# 01_MCU.net
KiCad netlist of a schematic drawn in Altium Designer
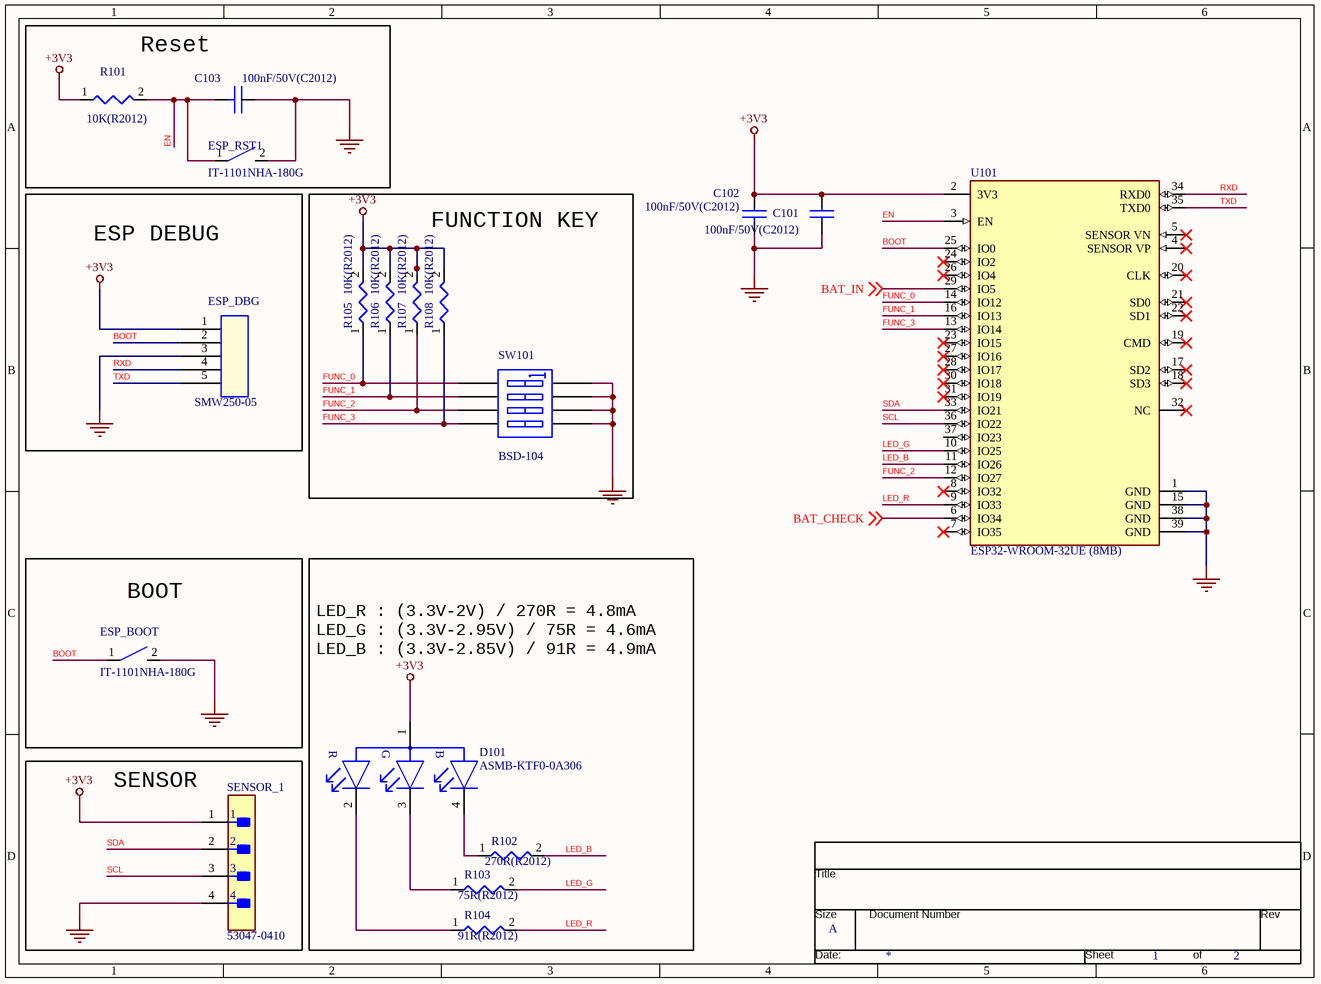
[diagram p0: 01_MCU.SchDoc]

(export (version "E")
  (design (tool "Eeschema 10.0.6"))
  (components
    (comp (ref "*")
      (value "TitleBlock0")
      (fields (field (name "PAGE COUNT") "2") (field (name "PAGE NUMBER") "1") (field (name "PAGE SIZE") "A"))
      (libsource (lib "*") (part "TitleBlock0"))
    )
    (comp (ref "C101") (value "100nF/50V(C2012)") (footprint "C2012") (libsource (lib "*") (part "CAP NP_0")))
    (comp (ref "C102") (value "100nF/50V(C2012)") (footprint "C2012") (libsource (lib "*") (part "CAP NP_0")))
    (comp (ref "C103") (value "100nF/50V(C2012)") (footprint "C2012") (libsource (lib "*") (part "C_0")))
    (comp (ref "D101")
      (value "ASMB-KTF0-0A306")
      (footprint "FP-PLCC-4-MFG")
      (description "LED RGB 4PLCC SMD")
      (fields
        (field (name "MANUFACTURER") "Broadcom")
        (field (name "OCTOPART") "https://octopart.com/asmb-ktf0-0a306-broadcom-87157377")
      )
      (libsource (lib "Altium Content Vault") (part "e0afb02c9a33798a4bdd6795f3df34c"))
    )
    (comp (ref "ESP_BOOT")
      (value "IT-1101NHA-180G")
      (footprint "SW_Tact_2p")
      (libsource (lib "*") (part "SWITCH"))
    )
    (comp (ref "ESP_DBG") (value "SMW250-05") (footprint "CON5267-05") (libsource (lib "*") (part "CON5")))
    (comp (ref "ESP_RST1")
      (value "IT-1101NHA-180G")
      (footprint "SW_Tact_2p")
      (libsource (lib "*") (part "SWITCH"))
    )
    (comp (ref "R101") (value "10K(R2012)") (footprint "R2012") (libsource (lib "*") (part "R_3")))
    (comp (ref "R102") (value "270R(R2012)") (footprint "R2012") (libsource (lib "*") (part "R_3")))
    (comp (ref "R103") (value "75R(R2012)") (footprint "R2012") (libsource (lib "*") (part "R_3")))
    (comp (ref "R104") (value "91R(R2012)") (footprint "R2012") (libsource (lib "*") (part "R_3")))
    (comp (ref "R105") (value "10K(R2012)") (footprint "R2012") (libsource (lib "*") (part "R_3")))
    (comp (ref "R106") (value "10K(R2012)") (footprint "R2012") (libsource (lib "*") (part "R_3")))
    (comp (ref "R107") (value "10K(R2012)") (footprint "R2012") (libsource (lib "*") (part "R_3")))
    (comp (ref "R108") (value "10K(R2012)") (footprint "R2012") (libsource (lib "*") (part "R_3")))
    (comp (ref "SENSOR_1")
      (value "53047-0410")
      (footprint "FP-53047-0410-MFG")
      (description "CONN HEADER VERT 4POS 1.25MM")
      (fields (field (name "VOLTAGE") "125V"))
      (libsource (lib "Altium Content Vault") (part "299a8cea1bdcbc3624fe62c390fa72c"))
    )
    (comp (ref "SW101") (value "BSD-104") (footprint "DIP_SW4") (libsource (lib "*") (part "SW DIP-4")))
    (comp (ref "U101")
      (value "ESP32-WROOM-32UE (8MB)")
      (footprint "FP-ESP32-WROOM-32U_16MB-MFG")
      (description "RX TXRX MODULE WIFI U.FL SMD")
      (libsource (lib "Components - 05.07.22 - 15.17") (part "CMP-194065-000029-1"))
    )
  )
  (nets
    (net (code "1") (name "+3V3") (class "Default")
      (node (ref "C101") (pin "1") (pinfunction "1_1") (pintype "passive"))
      (node (ref "C102") (pin "1") (pinfunction "1_1") (pintype "passive"))
      (node (ref "D101") (pin "1") (pinfunction "A_1") (pintype "passive"))
      (node (ref "ESP_DBG") (pin "1") (pinfunction "1_1") (pintype "passive"))
      (node (ref "R101") (pin "1") (pinfunction "1_1") (pintype "passive"))
      (node (ref "R105") (pin "2") (pinfunction "2_2") (pintype "passive"))
      (node (ref "R106") (pin "2") (pinfunction "2_2") (pintype "passive"))
      (node (ref "R107") (pin "2") (pinfunction "2_2") (pintype "passive"))
      (node (ref "R108") (pin "2") (pinfunction "2_2") (pintype "passive"))
      (node (ref "SENSOR_1") (pin "1") (pinfunction "1_1") (pintype "passive"))
      (node (ref "U101") (pin "2") (pinfunction "3V3_2") (pintype "power_in"))
    )
    (net (code "2") (name "/BOOT") (class "Default")
      (node (ref "ESP_BOOT") (pin "1") (pinfunction "1_1") (pintype "passive"))
      (node (ref "ESP_DBG") (pin "2") (pinfunction "2_2") (pintype "passive"))
      (node (ref "U101") (pin "25") (pinfunction "IO0_25") (pintype "bidirectional"))
    )
    (net (code "3") (name "/EN") (class "Default")
      (node (ref "C103") (pin "2") (pinfunction "2_2") (pintype "passive"))
      (node (ref "ESP_RST1") (pin "1") (pinfunction "1_1") (pintype "passive"))
      (node (ref "R101") (pin "2") (pinfunction "2_2") (pintype "passive"))
      (node (ref "U101") (pin "3") (pinfunction "EN_3") (pintype "input"))
    )
    (net (code "4") (name "/FUNC_0") (class "Default")
      (node (ref "R105") (pin "1") (pinfunction "1_1") (pintype "passive"))
      (node (ref "SW101") (pin "1") (pinfunction "A1_1") (pintype "passive"))
      (node (ref "U101") (pin "14") (pinfunction "IO12_14") (pintype "bidirectional"))
    )
    (net (code "5") (name "/FUNC_1") (class "Default")
      (node (ref "R106") (pin "1") (pinfunction "1_1") (pintype "passive"))
      (node (ref "SW101") (pin "2") (pinfunction "A2_2") (pintype "passive"))
      (node (ref "U101") (pin "16") (pinfunction "IO13_16") (pintype "bidirectional"))
    )
    (net (code "6") (name "/FUNC_2") (class "Default")
      (node (ref "R107") (pin "1") (pinfunction "1_1") (pintype "passive"))
      (node (ref "SW101") (pin "3") (pinfunction "A3_3") (pintype "passive"))
      (node (ref "U101") (pin "12") (pinfunction "IO27_12") (pintype "bidirectional"))
    )
    (net (code "7") (name "/FUNC_3") (class "Default")
      (node (ref "R108") (pin "1") (pinfunction "1_1") (pintype "passive"))
      (node (ref "SW101") (pin "4") (pinfunction "A4_4") (pintype "passive"))
      (node (ref "U101") (pin "13") (pinfunction "IO14_13") (pintype "bidirectional"))
    )
    (net (code "8") (name "/LED_B") (class "Default")
      (node (ref "R102") (pin "2") (pinfunction "2_2") (pintype "passive"))
      (node (ref "U101") (pin "11") (pinfunction "IO26_11") (pintype "bidirectional"))
    )
    (net (code "9") (name "/LED_G") (class "Default")
      (node (ref "R103") (pin "2") (pinfunction "2_2") (pintype "passive"))
      (node (ref "U101") (pin "10") (pinfunction "IO25_10") (pintype "bidirectional"))
    )
    (net (code "10") (name "/LED_R") (class "Default")
      (node (ref "R104") (pin "2") (pinfunction "2_2") (pintype "passive"))
      (node (ref "U101") (pin "9") (pinfunction "IO33_9") (pintype "bidirectional"))
    )
    (net (code "11") (name "/RXD") (class "Default")
      (node (ref "ESP_DBG") (pin "4") (pinfunction "4_4") (pintype "passive"))
      (node (ref "U101") (pin "34") (pinfunction "RXD0_34") (pintype "bidirectional"))
    )
    (net (code "12") (name "/SCL") (class "Default")
      (node (ref "SENSOR_1") (pin "3") (pinfunction "3_3") (pintype "passive"))
      (node (ref "U101") (pin "36") (pinfunction "IO22_36") (pintype "bidirectional"))
    )
    (net (code "13") (name "/SDA") (class "Default")
      (node (ref "SENSOR_1") (pin "2") (pinfunction "2_2") (pintype "passive"))
      (node (ref "U101") (pin "33") (pinfunction "IO21_33") (pintype "bidirectional"))
    )
    (net (code "14") (name "/TXD") (class "Default")
      (node (ref "ESP_DBG") (pin "5") (pinfunction "5_5") (pintype "passive"))
      (node (ref "U101") (pin "35") (pinfunction "TXD0_35") (pintype "bidirectional"))
    )
    (net (code "15") (name "BAT_CHECK") (class "Default")
      (node (ref "U101") (pin "6") (pinfunction "IO34_6") (pintype "bidirectional"))
    )
    (net (code "16") (name "BAT_IN") (class "Default")
      (node (ref "U101") (pin "29") (pinfunction "IO5_29") (pintype "bidirectional"))
    )
    (net (code "17") (name "GND") (class "Default")
      (node (ref "C101") (pin "2") (pinfunction "2_2") (pintype "passive"))
      (node (ref "C102") (pin "2") (pinfunction "2_2") (pintype "passive"))
      (node (ref "C103") (pin "1") (pinfunction "1_1") (pintype "passive"))
      (node (ref "ESP_BOOT") (pin "2") (pinfunction "2_2") (pintype "passive"))
      (node (ref "ESP_DBG") (pin "3") (pinfunction "3_3") (pintype "passive"))
      (node (ref "ESP_RST1") (pin "2") (pinfunction "2_2") (pintype "passive"))
      (node (ref "SENSOR_1") (pin "4") (pinfunction "4_4") (pintype "passive"))
      (node (ref "SW101") (pin "5") (pinfunction "B4_5") (pintype "passive"))
      (node (ref "SW101") (pin "6") (pinfunction "B3_6") (pintype "passive"))
      (node (ref "SW101") (pin "7") (pinfunction "B2_7") (pintype "passive"))
      (node (ref "SW101") (pin "8") (pinfunction "B1_8") (pintype "passive"))
      (node (ref "U101") (pin "1") (pinfunction "GND_1") (pintype "power_in"))
      (node (ref "U101") (pin "15") (pinfunction "GND_15") (pintype "power_in"))
      (node (ref "U101") (pin "38") (pinfunction "GND_38") (pintype "power_in"))
      (node (ref "U101") (pin "39") (pinfunction "GND_39") (pintype "power_in"))
    )
    (net (code "18") (name "Net-(D101-Blue_C)") (class "Default")
      (node (ref "D101") (pin "4") (pinfunction "Blue_C_4") (pintype "passive"))
      (node (ref "R102") (pin "1") (pinfunction "1_1") (pintype "passive"))
    )
    (net (code "19") (name "Net-(D101-Green_C)") (class "Default")
      (node (ref "D101") (pin "3") (pinfunction "Green_C_3") (pintype "passive"))
      (node (ref "R103") (pin "1") (pinfunction "1_1") (pintype "passive"))
    )
    (net (code "20") (name "Net-(D101-Red_C)") (class "Default")
      (node (ref "D101") (pin "2") (pinfunction "Red_C_2") (pintype "passive"))
      (node (ref "R104") (pin "1") (pinfunction "1_1") (pintype "passive"))
    )
    (net (code "21") (name "unconnected-(U101-CLK-Pad20)") (class "Default")
      (node (ref "U101") (pin "20") (pinfunction "CLK_20") (pintype "bidirectional+no_connect"))
    )
    (net (code "22") (name "unconnected-(U101-CMD-Pad19)") (class "Default")
      (node (ref "U101") (pin "19") (pinfunction "CMD_19") (pintype "bidirectional+no_connect"))
    )
    (net (code "23") (name "unconnected-(U101-IO2-Pad24)") (class "Default")
      (node (ref "U101") (pin "24") (pinfunction "IO2_24") (pintype "bidirectional+no_connect"))
    )
    (net (code "24") (name "unconnected-(U101-IO4-Pad26)") (class "Default")
      (node (ref "U101") (pin "26") (pinfunction "IO4_26") (pintype "bidirectional+no_connect"))
    )
    (net (code "25") (name "unconnected-(U101-IO15-Pad23)") (class "Default")
      (node (ref "U101") (pin "23") (pinfunction "IO15_23") (pintype "bidirectional+no_connect"))
    )
    (net (code "26") (name "unconnected-(U101-IO16-Pad27)") (class "Default")
      (node (ref "U101") (pin "27") (pinfunction "IO16_27") (pintype "bidirectional+no_connect"))
    )
    (net (code "27") (name "unconnected-(U101-IO17-Pad28)") (class "Default")
      (node (ref "U101") (pin "28") (pinfunction "IO17_28") (pintype "bidirectional+no_connect"))
    )
    (net (code "28") (name "unconnected-(U101-IO18-Pad30)") (class "Default")
      (node (ref "U101") (pin "30") (pinfunction "IO18_30") (pintype "bidirectional+no_connect"))
    )
    (net (code "29") (name "unconnected-(U101-IO19-Pad31)") (class "Default")
      (node (ref "U101") (pin "31") (pinfunction "IO19_31") (pintype "bidirectional+no_connect"))
    )
    (net (code "30") (name "unconnected-(U101-IO23-Pad37)") (class "Default")
      (node (ref "U101") (pin "37") (pinfunction "IO23_37") (pintype "bidirectional"))
    )
    (net (code "31") (name "unconnected-(U101-IO32-Pad8)") (class "Default")
      (node (ref "U101") (pin "8") (pinfunction "IO32_8") (pintype "bidirectional+no_connect"))
    )
    (net (code "32") (name "unconnected-(U101-IO35-Pad7)") (class "Default")
      (node (ref "U101") (pin "7") (pinfunction "IO35_7") (pintype "bidirectional+no_connect"))
    )
    (net (code "33") (name "unconnected-(U101-NC-Pad32)") (class "Default")
      (node (ref "U101") (pin "32") (pinfunction "NC_32") (pintype "passive+no_connect"))
    )
    (net (code "34") (name "unconnected-(U101-SD0-Pad21)") (class "Default")
      (node (ref "U101") (pin "21") (pinfunction "SD0_21") (pintype "bidirectional+no_connect"))
    )
    (net (code "35") (name "unconnected-(U101-SD1-Pad22)") (class "Default")
      (node (ref "U101") (pin "22") (pinfunction "SD1_22") (pintype "bidirectional+no_connect"))
    )
    (net (code "36") (name "unconnected-(U101-SD2-Pad17)") (class "Default")
      (node (ref "U101") (pin "17") (pinfunction "SD2_17") (pintype "bidirectional+no_connect"))
    )
    (net (code "37") (name "unconnected-(U101-SD3-Pad18)") (class "Default")
      (node (ref "U101") (pin "18") (pinfunction "SD3_18") (pintype "bidirectional+no_connect"))
    )
    (net (code "38") (name "unconnected-(U101-SENSOR_VN-Pad5)") (class "Default")
      (node (ref "U101") (pin "5") (pinfunction "SENSOR_VN_5") (pintype "input+no_connect"))
    )
    (net (code "39") (name "unconnected-(U101-SENSOR_VP-Pad4)") (class "Default")
      (node (ref "U101") (pin "4") (pinfunction "SENSOR_VP_4") (pintype "input+no_connect"))
    )
  )
)
